# CC1101RGPR.net
KiCad netlist of a schematic drawn in Altium Designer
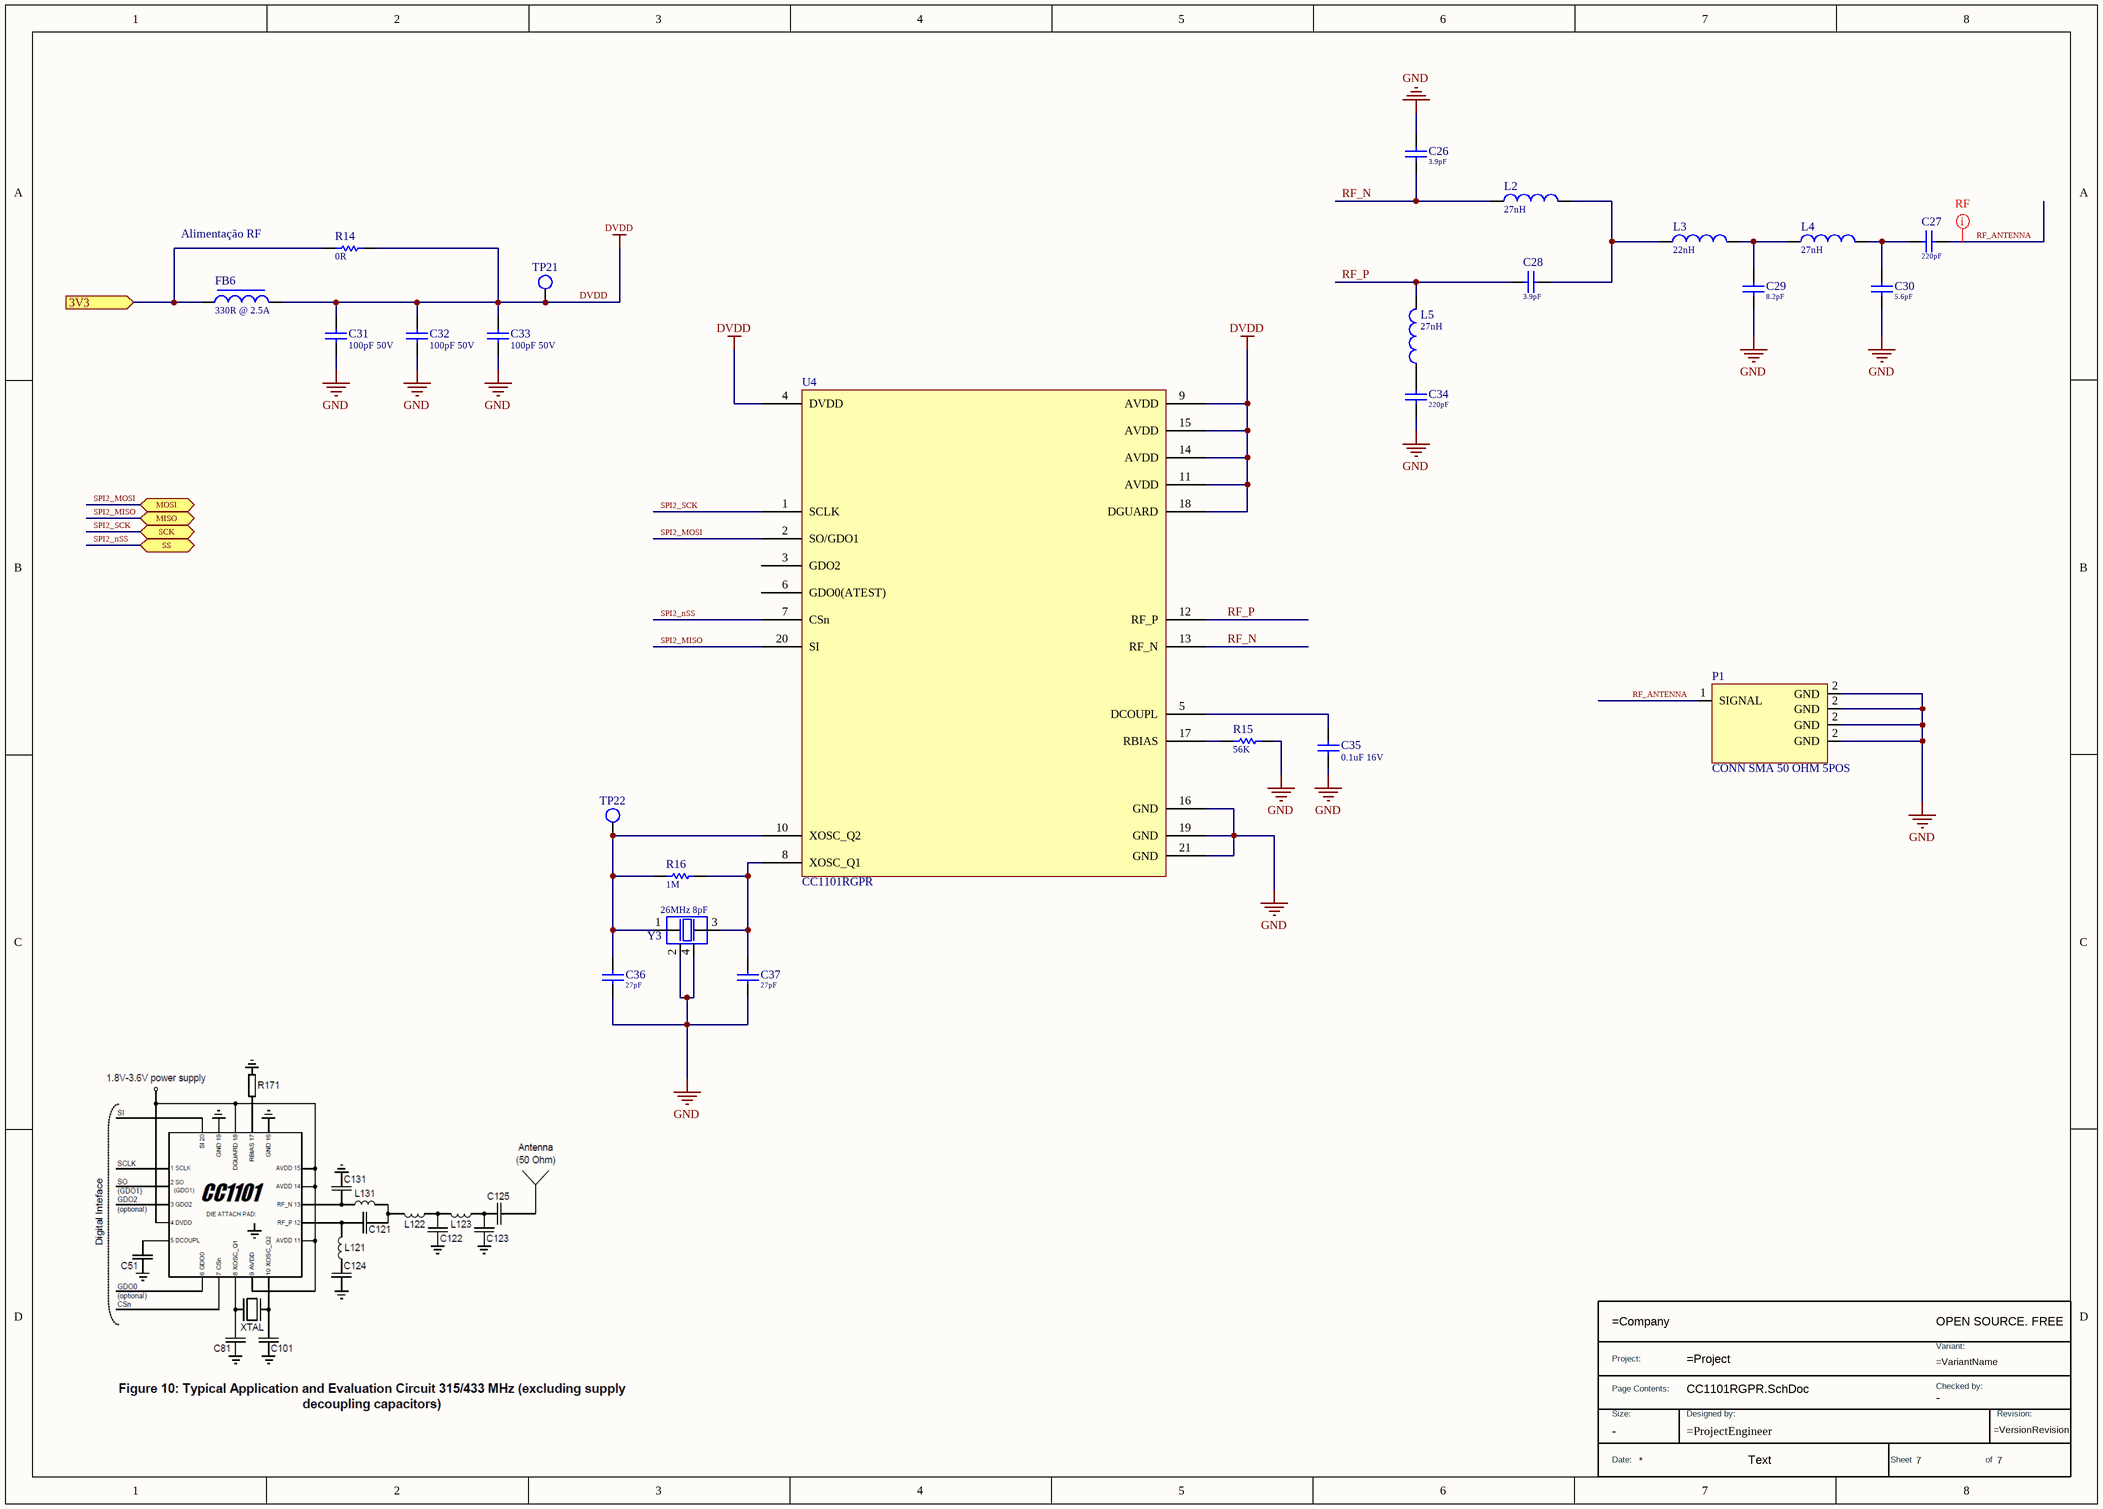
[diagram p0: CC1101RGPR.SchDoc]

(export (version "E")
  (design (tool "Eeschema 10.0.6"))
  (components
    (comp (ref "*")
      (value "TitleBlock")
      (description "Standard Title Block")
      (fields (field (name "SIZE") "-") (field (name "CHECKED BY") "-"))
      (libsource (lib "OBDH_Ed01r1") (part "TitleBlock"))
    )
    (comp (ref "C26")
      (value "GJM1555C1H3R9WB01D")
      (footprint "CAP 0402")
      (description "CAP CER 3.9PF 50V C0G/NP0 0402")
      (fields (field (name "MANUFACTURER") "Murata Electronics") (field (name "VALOR") "3.9pF"))
      (libsource (lib "OBDH_Ed02") (part "GJM1555C1H3R9WB01D"))
    )
    (comp (ref "C27")
      (value "GRM155R71H221JA01D")
      (footprint "CAP 0402")
      (description "CAP CER 220PF 50V X7R 0402")
      (fields (field (name "MANUFACTURER") "Murata Electronics") (field (name "VALOR") "220pF"))
      (libsource (lib "OBDH_Ed02") (part "GRM155R71H221JA01D"))
    )
    (comp (ref "C28")
      (value "GJM1555C1H3R9WB01D")
      (footprint "CAP 0402")
      (description "CAP CER 3.9PF 50V C0G/NP0 0402")
      (fields (field (name "MANUFACTURER") "Murata Electronics") (field (name "VALOR") "3.9pF"))
      (libsource (lib "OBDH_Ed02") (part "GJM1555C1H3R9WB01D"))
    )
    (comp (ref "C29")
      (value "GCM1555C1H8R2CA16D")
      (footprint "CAP 0402")
      (description "CAP CER 8.2PF 50V C0G/NP0 0402")
      (fields (field (name "MANUFACTURER") "Murata Electronics") (field (name "VALOR") "8.2pF"))
      (libsource (lib "OBDH_Ed02") (part "GCM1555C1H8R2CA16D"))
    )
    (comp (ref "C30")
      (value "GRM1555C1H5R6CA01D")
      (footprint "CAP 0402")
      (description "CAP CER 5.6PF 50V C0G/NP0 0402")
      (fields (field (name "MANUFACTURER") "Murata Electronics") (field (name "VALOR") "5.6pF"))
      (libsource (lib "OBDH_Ed02") (part "GRM1555C1H5R6CA01D"))
    )
    (comp (ref "C31")
      (value "CC0805JRNPO9BN101")
      (footprint "CAP_0805")
      (description "CAP CER 100PF 50V C0G/NPO 0805")
      (fields (field (name "MANUFACTURER") "YAGEO") (field (name "VALOR") "100pF 50V"))
      (libsource (lib "OBDH_Ed02") (part "CC0805JRNPO9BN101"))
    )
    (comp (ref "C32")
      (value "CC0805JRNPO9BN101")
      (footprint "CAP_0805")
      (description "CAP CER 100PF 50V C0G/NPO 0805")
      (fields (field (name "MANUFACTURER") "YAGEO") (field (name "VALOR") "100pF 50V"))
      (libsource (lib "OBDH_Ed02") (part "CC0805JRNPO9BN101"))
    )
    (comp (ref "C33")
      (value "CC0805JRNPO9BN101")
      (footprint "CAP_0805")
      (description "CAP CER 100PF 50V C0G/NPO 0805")
      (fields (field (name "MANUFACTURER") "YAGEO") (field (name "VALOR") "100pF 50V"))
      (libsource (lib "OBDH_Ed02") (part "CC0805JRNPO9BN101"))
    )
    (comp (ref "C34")
      (value "GRM155R71H221JA01D")
      (footprint "CAP 0402")
      (description "CAP CER 220PF 50V X7R 0402")
      (fields (field (name "MANUFACTURER") "Murata Electronics") (field (name "VALOR") "220pF"))
      (libsource (lib "OBDH_Ed02") (part "GRM155R71H221JA01D"))
    )
    (comp (ref "C35")
      (value "CL05B104KO5NNNC")
      (footprint "CAP_0805")
      (description "CAP CER 0.1UF 16V X5R 0805")
      (fields (field (name "MANUFACTURER") "Samsung Electro-Mechanics") (field (name "VALOR") "0.1uF 16V"))
      (libsource (lib "OBDH_Ed02") (part "CL05B104KO5NNNC"))
    )
    (comp (ref "C36")
      (value "GCM1555C1H270JA16D")
      (footprint "CAP 0402")
      (description "CAP CER 27PF 50V C0G/NP0 0402")
      (fields (field (name "MANUFACTURER") "Murata Electronics") (field (name "VALOR") "27pF"))
      (libsource (lib "OBDH_Ed02") (part "GCM1555C1H270JA16D"))
    )
    (comp (ref "C37")
      (value "GCM1555C1H270JA16D")
      (footprint "CAP 0402")
      (description "CAP CER 27PF 50V C0G/NP0 0402")
      (fields (field (name "MANUFACTURER") "Murata Electronics") (field (name "VALOR") "27pF"))
      (libsource (lib "OBDH_Ed02") (part "GCM1555C1H270JA16D"))
    )
    (comp (ref "FB6")
      (value "MPZ2012S331AT000")
      (footprint "IND_0805")
      (description "FERRITE BEAD 330 OHM 0805 1LN")
      (fields (field (name "MANUFACTURER") "TDK Corporation") (field (name "VALOR") "330R @ 2.5A"))
      (libsource (lib "OBDH_Ed02") (part "MPZ2012S331AT000"))
    )
    (comp (ref "L2")
      (value "27nH")
      (footprint "IND 0402")
      (description "FIXED IND 27NH 350MA 460MOHM SMD")
      (fields
        (field (name "MANUFACTURER") "Murata Electronics")
        (field (name "MANUFACTURER PART NUMBER") "LQG15HS27NH02D")
      )
      (libsource (lib "OBDH_Ed02") (part "LQG15HS27NH02D"))
    )
    (comp (ref "L3")
      (value "22nH")
      (footprint "IND 0402")
      (description "FIXED IND 22NH 350MA 580MOHM SMD")
      (fields
        (field (name "MANUFACTURER") "Murata Electronics")
        (field (name "MANUFACTURER PART NUMBER") "LQG15HN22NH02D")
      )
      (libsource (lib "OBDH_Ed02") (part "LQG15HN22NH02D"))
    )
    (comp (ref "L4")
      (value "27nH")
      (footprint "IND 0402")
      (description "FIXED IND 27NH 350MA 460MOHM SMD")
      (fields
        (field (name "MANUFACTURER") "Murata Electronics")
        (field (name "MANUFACTURER PART NUMBER") "LQG15HS27NH02D")
      )
      (libsource (lib "OBDH_Ed02") (part "LQG15HS27NH02D"))
    )
    (comp (ref "L5")
      (value "27nH")
      (footprint "IND 0402")
      (description "FIXED IND 27NH 350MA 460MOHM SMD")
      (fields
        (field (name "MANUFACTURER") "Murata Electronics")
        (field (name "MANUFACTURER PART NUMBER") "LQG15HS27NH02D")
      )
      (libsource (lib "OBDH_Ed02") (part "LQG15HS27NH02D"))
    )
    (comp (ref "P1")
      (value "CONN SMA 50 OHM 5POS")
      (footprint "CONN PTH SMA JACK CONSMA002-L-G")
      (description "CONN SMA JACK R/A 50OHM PCB")
      (libsource (lib "OBDH_Ed02") (part "CONN SMA 50 OHM 5POS"))
    )
    (comp (ref "R14")
      (value "RC0805JR-070RL")
      (footprint "RES_0805")
      (description "RES 0 OHM JUMPER 1/8W 0805")
      (fields (field (name "MANUFACTURER") "YAGEO") (field (name "VALOR") "0R"))
      (libsource (lib "OBDH_Ed02") (part "RC0805JR-070RL"))
    )
    (comp (ref "R15")
      (value "**CRCW080562K0JNEA")
      (footprint "RES_0805")
      (description "RES SMD 56K OHM 5% 1/8W 0805")
      (fields
        (field (name "MANUFACTURER") "YAGEO")
        (field (name "MANUFACTURER PART NUMBER") "CRCW080562K0JNEA")
        (field (name "VALOR") "56K")
      )
      (libsource (lib "OBDH_Ed02") (part "**CRCW080562K0JNEA"))
    )
    (comp (ref "R16")
      (value "CRCW08051M00JNEA")
      (footprint "RES 0402")
      (description "RES SMD 1M OHM 5% 1/8W 0805")
      (fields (field (name "MANUFACTURER") "Vishay Intertech") (field (name "VALOR") "1M"))
      (libsource (lib "OBDH_Ed02") (part "CRCW08051M00JNEA"))
    )
    (comp (ref "TP21")
      (value "TEST_POINT_1.5MM")
      (footprint "TESTPOINT_1.5MM")
      (description "TEST_POINT")
      (libsource (lib "OBDH_Ed02") (part "TEST_POINT_1.5MM"))
    )
    (comp (ref "TP22")
      (value "TEST_POINT_1.5MM")
      (footprint "TESTPOINT_1.5MM")
      (description "TEST_POINT")
      (libsource (lib "OBDH_Ed02") (part "TEST_POINT_1.5MM"))
    )
    (comp (ref "U4")
      (value "CC1101RGPR")
      (footprint "QLP-4x4")
      (description "IC RF TXRX ISM<1GHZ 20VFQFN")
      (libsource (lib "OBDH_Ed02") (part "CC1101RGPR"))
    )
    (comp (ref "Y3")
      (value "NX3225SA-26MHZ")
      (footprint "Crystal-4SMD")
      (description "CRYSTAL 26.0000MHZ 10PF SMD")
      (fields (field (name "MANUFACTURER") "NDK America, Inc.") (field (name "VALOR") "26MHz 8pF"))
      (libsource (lib "OBDH_Ed02") (part "NX3225SA-26MHZ"))
    )
  )
  (nets
    (net (code "1") (name "/3V3") (class "Default")
      (node (ref "FB6") (pin "1") (pinfunction "1_1") (pintype "passive"))
      (node (ref "R14") (pin "1") (pinfunction "1_1") (pintype "passive"))
    )
    (net (code "2") (name "/RF_ANTENNA") (class "Default")
      (node (ref "C27") (pin "2") (pinfunction "2_2") (pintype "passive"))
      (node (ref "P1") (pin "1") (pinfunction "SIGNAL_1") (pintype "passive"))
    )
    (net (code "3") (name "/RF_N") (class "Default")
      (node (ref "C26") (pin "1") (pinfunction "1_1") (pintype "passive"))
      (node (ref "L2") (pin "1") (pinfunction "1_1") (pintype "passive"))
      (node (ref "U4") (pin "13") (pinfunction "RF_N_13") (pintype "passive"))
    )
    (net (code "4") (name "/RF_P") (class "Default")
      (node (ref "C28") (pin "1") (pinfunction "1_1") (pintype "passive"))
      (node (ref "L5") (pin "2") (pinfunction "2_2") (pintype "passive"))
      (node (ref "U4") (pin "12") (pinfunction "RF_P_12") (pintype "passive"))
    )
    (net (code "5") (name "/SPI2_MISO") (class "Default")
      (node (ref "U4") (pin "20") (pinfunction "SI_20") (pintype "passive"))
    )
    (net (code "6") (name "/SPI2_MOSI") (class "Default")
      (node (ref "U4") (pin "2") (pinfunction "SO/GDO1_2") (pintype "passive"))
    )
    (net (code "7") (name "/SPI2_SCK") (class "Default")
      (node (ref "U4") (pin "1") (pinfunction "SCLK_1") (pintype "passive"))
    )
    (net (code "8") (name "/SPI2_nSS") (class "Default")
      (node (ref "U4") (pin "7") (pinfunction "CSn_7") (pintype "passive"))
    )
    (net (code "9") (name "DVDD") (class "Default")
      (node (ref "C31") (pin "2") (pinfunction "2_2") (pintype "passive"))
      (node (ref "C32") (pin "2") (pinfunction "2_2") (pintype "passive"))
      (node (ref "C33") (pin "2") (pinfunction "2_2") (pintype "passive"))
      (node (ref "FB6") (pin "2") (pinfunction "2_2") (pintype "passive"))
      (node (ref "R14") (pin "2") (pinfunction "2_2") (pintype "passive"))
      (node (ref "TP21") (pin "1") (pinfunction "1_1") (pintype "passive"))
      (node (ref "U4") (pin "11") (pinfunction "AVDD_11") (pintype "passive"))
      (node (ref "U4") (pin "14") (pinfunction "AVDD_14") (pintype "passive"))
      (node (ref "U4") (pin "15") (pinfunction "AVDD_15") (pintype "passive"))
      (node (ref "U4") (pin "18") (pinfunction "DGUARD_18") (pintype "passive"))
      (node (ref "U4") (pin "4") (pinfunction "DVDD_4") (pintype "passive"))
      (node (ref "U4") (pin "9") (pinfunction "AVDD_9") (pintype "passive"))
    )
    (net (code "10") (name "GND") (class "Default")
      (node (ref "C26") (pin "2") (pinfunction "2_2") (pintype "passive"))
      (node (ref "C29") (pin "2") (pinfunction "2_2") (pintype "passive"))
      (node (ref "C30") (pin "1") (pinfunction "1_1") (pintype "passive"))
      (node (ref "C31") (pin "1") (pinfunction "1_1") (pintype "passive"))
      (node (ref "C32") (pin "1") (pinfunction "1_1") (pintype "passive"))
      (node (ref "C33") (pin "1") (pinfunction "1_1") (pintype "passive"))
      (node (ref "C34") (pin "1") (pinfunction "1_1") (pintype "passive"))
      (node (ref "C35") (pin "1") (pinfunction "1_1") (pintype "passive"))
      (node (ref "C36") (pin "1") (pinfunction "1_1") (pintype "passive"))
      (node (ref "C37") (pin "1") (pinfunction "1_1") (pintype "passive"))
      (node (ref "P1") (pin "2") (pinfunction "GND_2") (pintype "power_in"))
      (node (ref "R15") (pin "2") (pinfunction "2_2") (pintype "passive"))
      (node (ref "U4") (pin "16") (pinfunction "GND_16") (pintype "passive"))
      (node (ref "U4") (pin "19") (pinfunction "GND_19") (pintype "passive"))
      (node (ref "U4") (pin "21") (pinfunction "GND_21") (pintype "passive"))
      (node (ref "Y3") (pin "2") (pinfunction "2_2") (pintype "passive"))
      (node (ref "Y3") (pin "4") (pinfunction "4_4") (pintype "passive"))
    )
    (net (code "11") (name "Net-(C27-Pad1)") (class "Default")
      (node (ref "C27") (pin "1") (pinfunction "1_1") (pintype "passive"))
      (node (ref "C30") (pin "2") (pinfunction "2_2") (pintype "passive"))
      (node (ref "L4") (pin "2") (pinfunction "2_2") (pintype "passive"))
    )
    (net (code "12") (name "Net-(C28-Pad2)") (class "Default")
      (node (ref "C28") (pin "2") (pinfunction "2_2") (pintype "passive"))
      (node (ref "L2") (pin "2") (pinfunction "2_2") (pintype "passive"))
      (node (ref "L3") (pin "1") (pinfunction "1_1") (pintype "passive"))
    )
    (net (code "13") (name "Net-(C29-Pad1)") (class "Default")
      (node (ref "C29") (pin "1") (pinfunction "1_1") (pintype "passive"))
      (node (ref "L3") (pin "2") (pinfunction "2_2") (pintype "passive"))
      (node (ref "L4") (pin "1") (pinfunction "1_1") (pintype "passive"))
    )
    (net (code "14") (name "Net-(C34-Pad2)") (class "Default")
      (node (ref "C34") (pin "2") (pinfunction "2_2") (pintype "passive"))
      (node (ref "L5") (pin "1") (pinfunction "1_1") (pintype "passive"))
    )
    (net (code "15") (name "Net-(U4-DCOUPL)") (class "Default")
      (node (ref "C35") (pin "2") (pinfunction "2_2") (pintype "passive"))
      (node (ref "U4") (pin "5") (pinfunction "DCOUPL_5") (pintype "passive"))
    )
    (net (code "16") (name "Net-(U4-RBIAS)") (class "Default")
      (node (ref "R15") (pin "1") (pinfunction "1_1") (pintype "passive"))
      (node (ref "U4") (pin "17") (pinfunction "RBIAS_17") (pintype "passive"))
    )
    (net (code "17") (name "Net-(U4-XOSC_Q1)") (class "Default")
      (node (ref "C37") (pin "2") (pinfunction "2_2") (pintype "passive"))
      (node (ref "R16") (pin "2") (pinfunction "2_2") (pintype "passive"))
      (node (ref "U4") (pin "8") (pinfunction "XOSC_Q1_8") (pintype "passive"))
      (node (ref "Y3") (pin "3") (pinfunction "3_3") (pintype "passive"))
    )
    (net (code "18") (name "Net-(U4-XOSC_Q2)") (class "Default")
      (node (ref "C36") (pin "2") (pinfunction "2_2") (pintype "passive"))
      (node (ref "R16") (pin "1") (pinfunction "1_1") (pintype "passive"))
      (node (ref "TP22") (pin "1") (pinfunction "1_1") (pintype "passive"))
      (node (ref "U4") (pin "10") (pinfunction "XOSC_Q2_10") (pintype "passive"))
      (node (ref "Y3") (pin "1") (pinfunction "1_1") (pintype "passive"))
    )
    (net (code "19") (name "unconnected-(U4-GDO0(ATEST)-Pad6)") (class "Default")
      (node (ref "U4") (pin "6") (pinfunction "GDO0(ATEST)_6") (pintype "passive"))
    )
    (net (code "20") (name "unconnected-(U4-GDO2-Pad3)") (class "Default")
      (node (ref "U4") (pin "3") (pinfunction "GDO2_3") (pintype "passive"))
    )
  )
)
